# MMA7455L-v12.net
KiCad netlist of a schematic drawn in EAGLE
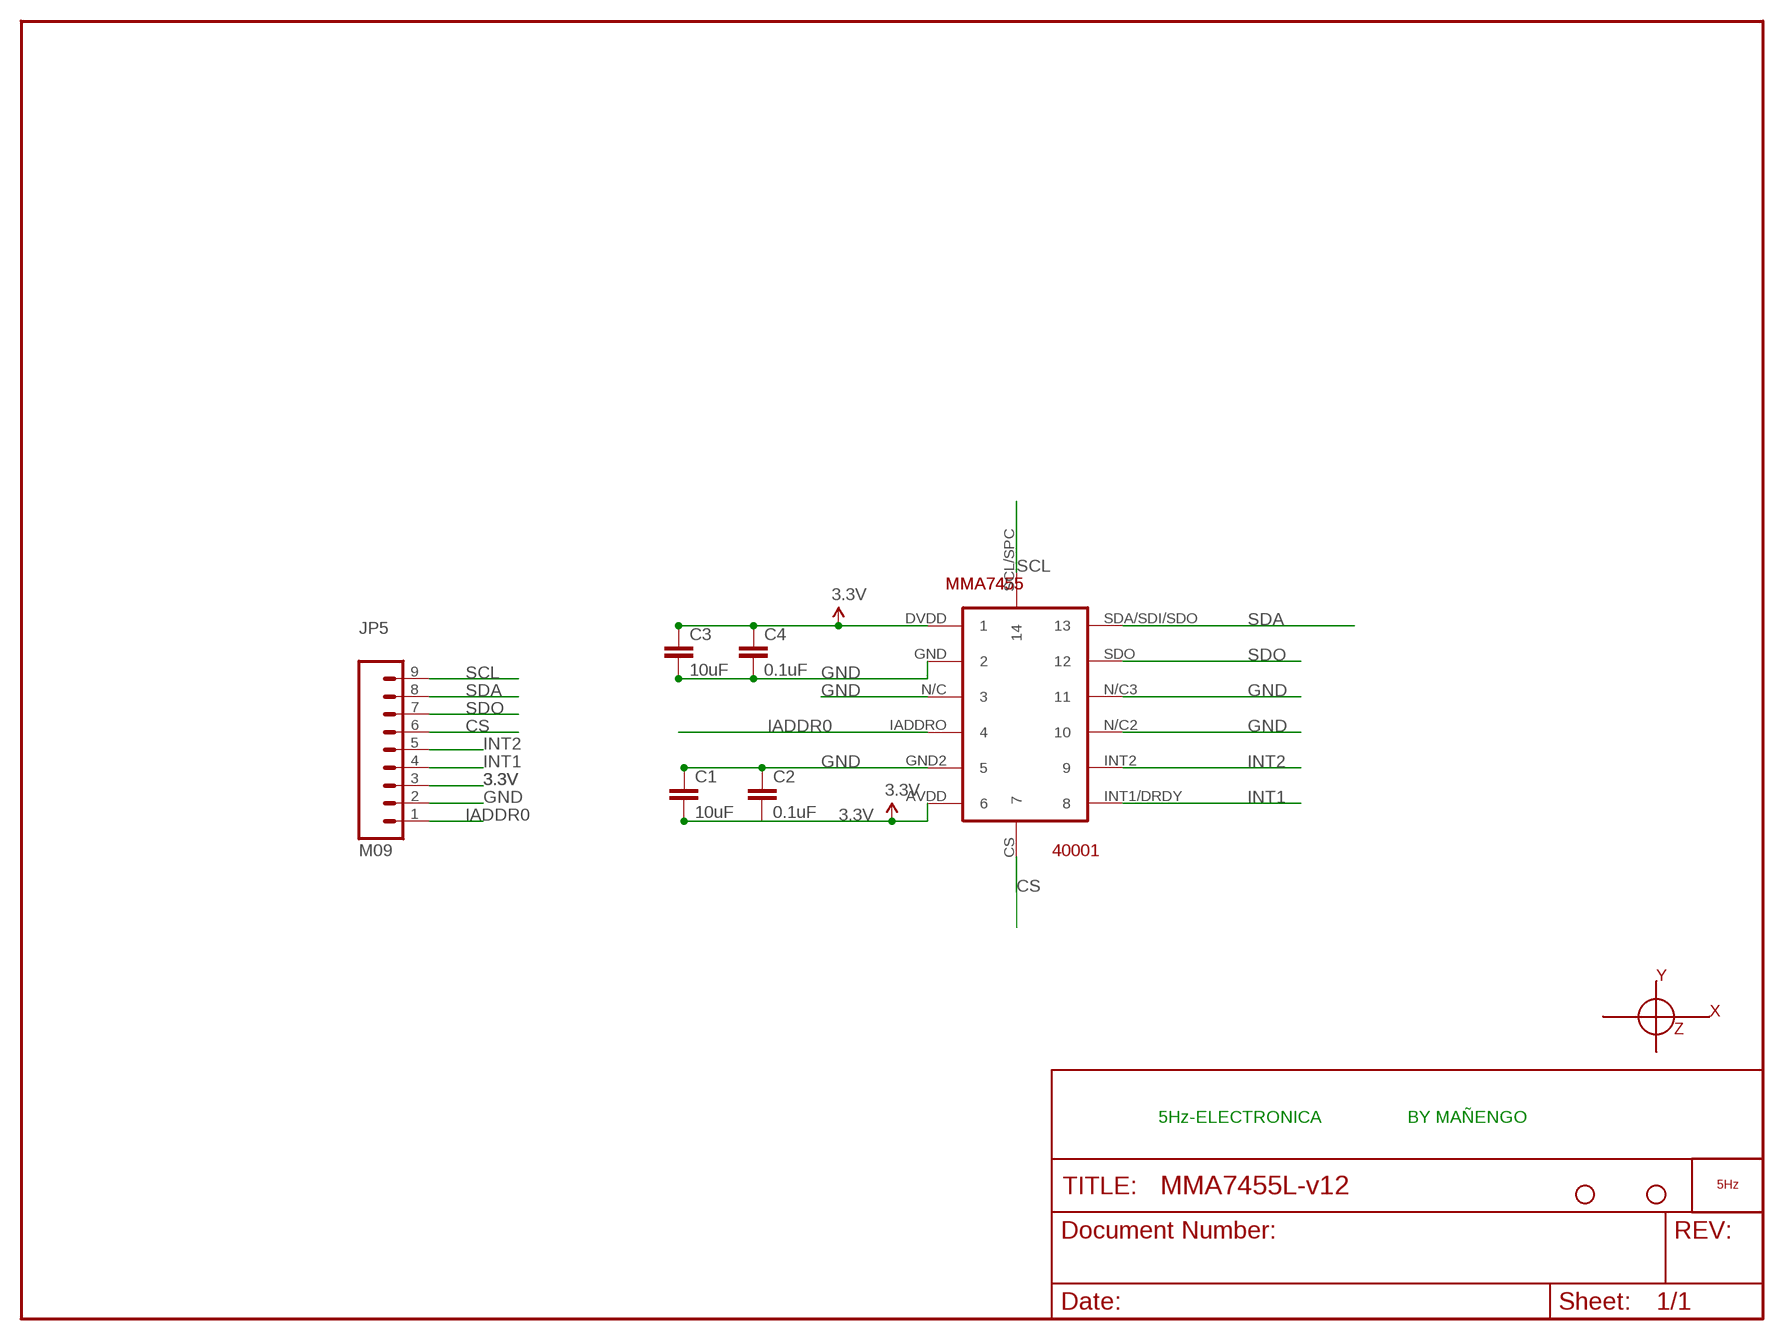
[diagram p0: schematic, sheet 1]

(export (version "E")
  (design (tool "Eeschema 10.0.6"))
  (components
    (comp (ref "C1")
      (value "10uF")
      (footprint "eagle-import:0603-CAP")
      (libsource (lib "eagle-import") (part "CAP0603-CAP"))
    )
    (comp (ref "C2")
      (value "0.1uF")
      (footprint "eagle-import:0603-CAP")
      (libsource (lib "eagle-import") (part "CAP0603-CAP"))
    )
    (comp (ref "C3")
      (value "10uF")
      (footprint "eagle-import:0603-CAP")
      (libsource (lib "eagle-import") (part "CAP0603-CAP"))
    )
    (comp (ref "C4")
      (value "0.1uF")
      (footprint "eagle-import:0603-CAP")
      (libsource (lib "eagle-import") (part "CAP0603-CAP"))
    )
    (comp (ref "JP3")
      (value "STAND-OFF")
      (footprint "eagle-import:STAND-OFF")
      (libsource (lib "eagle-import") (part "STAND-OFF"))
    )
    (comp (ref "JP4")
      (value "STAND-OFF")
      (footprint "eagle-import:STAND-OFF")
      (libsource (lib "eagle-import") (part "STAND-OFF"))
    )
    (comp (ref "JP5")
      (value "M09")
      (footprint "eagle-import:1X09")
      (libsource (lib "eagle-import") (part "M09"))
    )
    (comp (ref "LOGO1")
      (value "LOGO_5HZ_H_10MM")
      (footprint "eagle-import:5HZ_LOGO_H_10MM")
      (libsource (lib "eagle-import") (part "LOGO_5HZ_H_10MM"))
    )
    (comp (ref "MMA7455")
      (value "40001")
      (footprint "eagle-import:MMA7455L")
      (libsource (lib "eagle-import") (part "MMA7455L"))
    )
    (comp (ref "U$3")
      (value "EJES_CARTESIANO_5MM")
      (footprint "eagle-import:EJE_CARTESIANO_5MM")
      (libsource (lib "eagle-import") (part "EJES_CARTESIANO_5MM"))
    )
  )
  (nets
    (net (code "1") (name "/CS") (class "Default")
      (node (ref "JP5") (pin "6") (pinfunction "6_6") (pintype "passive"))
      (node (ref "MMA7455") (pin "CS") (pinfunction "7_CS") (pintype "bidirectional"))
    )
    (net (code "2") (name "/GND") (class "Default")
      (node (ref "C1") (pin "1") (pinfunction "1_1") (pintype "passive"))
      (node (ref "C2") (pin "1") (pinfunction "1_1") (pintype "passive"))
      (node (ref "C3") (pin "2") (pinfunction "2_2") (pintype "passive"))
      (node (ref "C4") (pin "2") (pinfunction "2_2") (pintype "passive"))
      (node (ref "JP5") (pin "2") (pinfunction "2_2") (pintype "passive"))
      (node (ref "MMA7455") (pin "GND") (pinfunction "2_GND") (pintype "bidirectional"))
      (node (ref "MMA7455") (pin "GND2") (pinfunction "5_GND2") (pintype "bidirectional"))
      (node (ref "MMA7455") (pin "N/C") (pinfunction "3_N/C") (pintype "bidirectional"))
      (node (ref "MMA7455") (pin "N/C2") (pinfunction "10_N/C2") (pintype "bidirectional"))
      (node (ref "MMA7455") (pin "N/C3") (pinfunction "11_N/C3") (pintype "bidirectional"))
    )
    (net (code "3") (name "/IADDR0") (class "Default")
      (node (ref "JP5") (pin "1") (pinfunction "1_1") (pintype "passive"))
      (node (ref "MMA7455") (pin "IADDRO") (pinfunction "4_IADDRO") (pintype "bidirectional"))
    )
    (net (code "4") (name "/INT1") (class "Default")
      (node (ref "JP5") (pin "4") (pinfunction "4_4") (pintype "passive"))
      (node (ref "MMA7455") (pin "INT1/DRDY") (pinfunction "8_INT1/DRDY") (pintype "bidirectional"))
    )
    (net (code "5") (name "/INT2") (class "Default")
      (node (ref "JP5") (pin "5") (pinfunction "5_5") (pintype "passive"))
      (node (ref "MMA7455") (pin "INT2") (pinfunction "9_INT2") (pintype "bidirectional"))
    )
    (net (code "6") (name "/SCL") (class "Default")
      (node (ref "JP5") (pin "9") (pinfunction "9_9") (pintype "passive"))
      (node (ref "MMA7455") (pin "SCL/SPC") (pinfunction "14_SCL/SPC") (pintype "bidirectional"))
    )
    (net (code "7") (name "/SDA") (class "Default")
      (node (ref "JP5") (pin "8") (pinfunction "8_8") (pintype "passive"))
      (node (ref "MMA7455") (pin "SDA/SDI/SDO") (pinfunction "13_SDA/SDI/SDO") (pintype "bidirectional"))
    )
    (net (code "8") (name "/SDO") (class "Default")
      (node (ref "JP5") (pin "7") (pinfunction "7_7") (pintype "passive"))
      (node (ref "MMA7455") (pin "SDO") (pinfunction "12_SDO") (pintype "bidirectional"))
    )
    (net (code "9") (name "3.3V") (class "Default")
      (node (ref "C1") (pin "2") (pinfunction "2_2") (pintype "passive"))
      (node (ref "C2") (pin "2") (pinfunction "2_2") (pintype "passive"))
      (node (ref "C3") (pin "1") (pinfunction "1_1") (pintype "passive"))
      (node (ref "C4") (pin "1") (pinfunction "1_1") (pintype "passive"))
      (node (ref "JP5") (pin "3") (pinfunction "3_3") (pintype "passive"))
      (node (ref "MMA7455") (pin "AVDD") (pinfunction "6_AVDD") (pintype "bidirectional"))
      (node (ref "MMA7455") (pin "DVDD") (pinfunction "1_DVDD") (pintype "bidirectional"))
    )
  )
)
